# MCU.net
KiCad netlist of a schematic drawn in Altium Designer
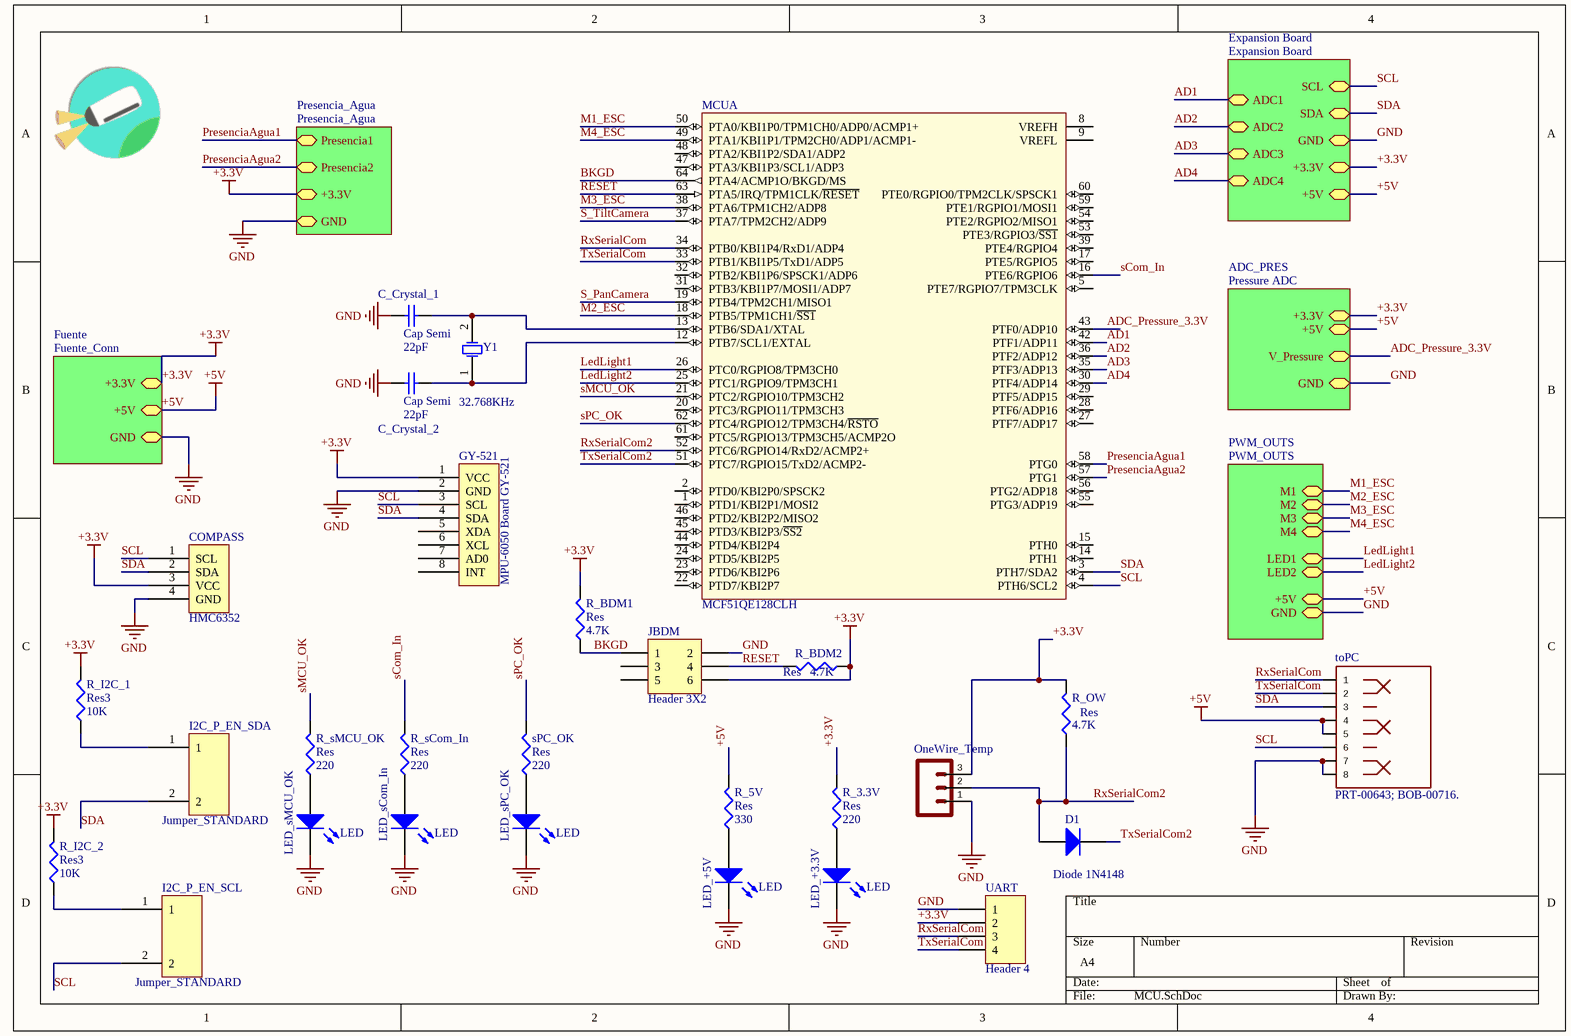
[diagram p0: MCU.SchDoc]

(export (version "E")
  (design (tool "Eeschema 10.0.6"))
  (components
    (comp (ref "COMPASS")
      (value "HMC6352")
      (footprint "HMC6352_SF")
      (libsource (lib "XSUB_COMP") (part "HMC6352"))
    )
    (comp (ref "C_Crystal_1")
      (value "Cap Semi")
      (footprint "1608[0603]")
      (description "Capacitor (Semiconductor SIM Model)")
      (fields (field (name "ALTIUM_VALUE") "22pF") (field (name "PUBLISHER") "Altium Limited"))
      (libsource (lib "Miscellaneous Devices") (part "Cap Semi"))
    )
    (comp (ref "C_Crystal_2")
      (value "Cap Semi")
      (footprint "1608[0603]")
      (description "Capacitor (Semiconductor SIM Model)")
      (fields (field (name "ALTIUM_VALUE") "22pF") (field (name "PUBLISHER") "Altium Limited"))
      (libsource (lib "Miscellaneous Devices") (part "Cap Semi"))
    )
    (comp (ref "D1")
      (value "Diode 1N4148")
      (footprint "DO-35")
      (description "High Conductance Fast Diode")
      (fields (field (name "PUBLISHER") "Altium Limited"))
      (libsource (lib "Miscellaneous Devices") (part "Diode 1N4148"))
    )
    (comp (ref "GY-521")
      (value "MPU-6050 Board GY-521")
      (footprint "GY-521")
      (libsource (lib "XSUB_COMP") (part "GY-521"))
    )
    (comp (ref "I2C_P_EN_SCL")
      (value "Jumper_STANDARD")
      (footprint "HDR1X2")
      (libsource (lib "XSUB_COMP") (part "Jumper_STANDAR"))
    )
    (comp (ref "I2C_P_EN_SDA")
      (value "Jumper_STANDARD")
      (footprint "HDR1X2")
      (libsource (lib "XSUB_COMP") (part "Jumper_STANDAR"))
    )
    (comp (ref "JBDM")
      (value "Header 3X2")
      (footprint "HDR2X3")
      (description "Header, 3-Pin, Dual row")
      (fields (field (name "PUBLISHER") "Altium Limited"))
      (libsource (lib "Miscellaneous Connectors") (part "Header 3X2"))
    )
    (comp (ref "LED_+3.3V")
      (value "LED")
      (footprint "3.2X1.6X1.1")
      (description "Typical RED, GREEN, YELLOW, AMBER GaAs LED")
      (fields (field (name "PUBLISHER") "Altium Limited"))
      (libsource (lib "Miscellaneous Devices") (part "LED2"))
    )
    (comp (ref "LED_+5V")
      (value "LED")
      (footprint "3.2X1.6X1.1")
      (description "Typical RED, GREEN, YELLOW, AMBER GaAs LED")
      (fields (field (name "PUBLISHER") "Altium Limited"))
      (libsource (lib "Miscellaneous Devices") (part "LED2"))
    )
    (comp (ref "LED_sCom_In")
      (value "LED")
      (footprint "3.2X1.6X1.1")
      (description "Typical RED, GREEN, YELLOW, AMBER GaAs LED")
      (fields (field (name "PUBLISHER") "Altium Limited"))
      (libsource (lib "Miscellaneous Devices") (part "LED2"))
    )
    (comp (ref "LED_sMCU_OK")
      (value "LED")
      (footprint "3.2X1.6X1.1")
      (description "Typical RED, GREEN, YELLOW, AMBER GaAs LED")
      (fields (field (name "PUBLISHER") "Altium Limited"))
      (libsource (lib "Miscellaneous Devices") (part "LED2"))
    )
    (comp (ref "LED_sPC_OK")
      (value "LED")
      (footprint "3.2X1.6X1.1")
      (description "Typical RED, GREEN, YELLOW, AMBER GaAs LED")
      (fields (field (name "PUBLISHER") "Altium Limited"))
      (libsource (lib "Miscellaneous Devices") (part "LED2"))
    )
    (comp (ref "MCU")
      (value "MCF51QE128CLH")
      (footprint "840F-02_N")
      (description "MCF51QE128 ColdFire V1 Microcontroller, 32-Bit, 128KB Flash, 8KB RAM, -40°C to 85°C, 64-Pin LQFP")
      (libsource (lib "Freescale Semiconductor ColdFire MCU") (part "MCF51QE128CLH"))
    )
    (comp (ref "OneWire_Temp")
      (value "~")
      (footprint "SCREWTERMINAL-5MM-3")
      (libsource (lib "SparkFun-Connectors") (part "M03-SCREW-5MM"))
    )
    (comp (ref "R_3.3V")
      (value "Res")
      (footprint "RESC6332")
      (description "Resistor")
      (fields (field (name "ALTIUM_VALUE") "220") (field (name "PUBLISHER") "Altium Limited"))
      (libsource (lib "Miscellaneous Devices") (part "Res3"))
    )
    (comp (ref "R_5V")
      (value "Res")
      (footprint "RESC6332")
      (description "Resistor")
      (fields (field (name "ALTIUM_VALUE") "330") (field (name "PUBLISHER") "Altium Limited"))
      (libsource (lib "Miscellaneous Devices") (part "Res3"))
    )
    (comp (ref "R_BDM1")
      (value "Res")
      (footprint "RESC6332")
      (description "Resistor")
      (fields (field (name "ALTIUM_VALUE") "4.7K") (field (name "PUBLISHER") "Altium Limited"))
      (libsource (lib "Miscellaneous Devices") (part "Res3"))
    )
    (comp (ref "R_BDM2")
      (value "Res")
      (footprint "RESC6332")
      (description "Resistor")
      (fields (field (name "ALTIUM_VALUE") "4.7K") (field (name "PUBLISHER") "Altium Limited"))
      (libsource (lib "Miscellaneous Devices") (part "Res3"))
    )
    (comp (ref "R_I2C_1")
      (value "Res3")
      (footprint "RESC6332")
      (description "Resistor")
      (fields (field (name "ALTIUM_VALUE") "10K") (field (name "PUBLISHER") "Altium Limited"))
      (libsource (lib "Miscellaneous Devices") (part "Res3"))
    )
    (comp (ref "R_I2C_2")
      (value "Res3")
      (footprint "RESC6332")
      (description "Resistor")
      (fields (field (name "ALTIUM_VALUE") "10K") (field (name "PUBLISHER") "Altium Limited"))
      (libsource (lib "Miscellaneous Devices") (part "Res3"))
    )
    (comp (ref "R_OW")
      (value "Res")
      (footprint "RESC6332")
      (description "Resistor")
      (fields (field (name "ALTIUM_VALUE") "4.7K") (field (name "PUBLISHER") "Altium Limited"))
      (libsource (lib "Miscellaneous Devices") (part "Res3"))
    )
    (comp (ref "R_sCom_In")
      (value "Res")
      (footprint "RESC6332")
      (description "Resistor")
      (fields (field (name "ALTIUM_VALUE") "220") (field (name "PUBLISHER") "Altium Limited"))
      (libsource (lib "Miscellaneous Devices") (part "Res3"))
    )
    (comp (ref "R_sMCU_OK")
      (value "Res")
      (footprint "RESC6332")
      (description "Resistor")
      (fields (field (name "ALTIUM_VALUE") "220") (field (name "PUBLISHER") "Altium Limited"))
      (libsource (lib "Miscellaneous Devices") (part "Res3"))
    )
    (comp (ref "sPC_OK")
      (value "Res")
      (footprint "RESC6332")
      (description "Resistor")
      (fields (field (name "ALTIUM_VALUE") "220") (field (name "PUBLISHER") "Altium Limited"))
      (libsource (lib "Miscellaneous Devices") (part "Res3"))
    )
    (comp (ref "toPC")
      (value "PRT-00643; BOB-00716.")
      (footprint "RJ45-8")
      (libsource (lib "SparkFun-Connectors") (part "RJ45-8PTH"))
    )
    (comp (ref "UART")
      (value "Header 4")
      (footprint "HDR1X4")
      (description "Header, 4-Pin")
      (fields (field (name "PUBLISHER") "Altium Limited"))
      (libsource (lib "Miscellaneous Connectors") (part "Header 4"))
    )
    (comp (ref "Y1")
      (value "32.768KHz")
      (footprint "R38")
      (description "Crystal Oscillator")
      (fields (field (name "PUBLISHER") "Altium Limited"))
      (libsource (lib "Miscellaneous Devices") (part "XTAL"))
    )
  )
  (nets
    (net (code "1") (name "+3.3V") (class "Default")
      (node (ref "COMPASS") (pin "3") (pinfunction "VCC_3") (pintype "passive"))
      (node (ref "GY-521") (pin "1") (pinfunction "VCC_1") (pintype "power_in"))
      (node (ref "JBDM") (pin "6") (pinfunction "6_6") (pintype "passive"))
      (node (ref "OneWire_Temp") (pin "3") (pinfunction "3_3") (pintype "passive"))
      (node (ref "R_3.3V") (pin "2") (pinfunction "2_2") (pintype "passive"))
      (node (ref "R_BDM1") (pin "2") (pinfunction "2_2") (pintype "passive"))
      (node (ref "R_BDM2") (pin "1") (pinfunction "1_1") (pintype "passive"))
      (node (ref "R_I2C_1") (pin "2") (pinfunction "2_2") (pintype "passive"))
      (node (ref "R_I2C_2") (pin "2") (pinfunction "2_2") (pintype "passive"))
      (node (ref "R_OW") (pin "2") (pinfunction "2_2") (pintype "passive"))
      (node (ref "UART") (pin "2") (pinfunction "2_2") (pintype "passive"))
    )
    (net (code "2") (name "+5V") (class "Default")
      (node (ref "R_5V") (pin "2") (pinfunction "2_2") (pintype "passive"))
      (node (ref "toPC") (pin "4") (pinfunction "4_4") (pintype "passive"))
      (node (ref "toPC") (pin "5") (pinfunction "5_5") (pintype "passive"))
    )
    (net (code "3") (name "/AD1") (class "Default")
      (node (ref "MCU") (pin "42") (pinfunction "PTF1/ADP11_42") (pintype "bidirectional"))
    )
    (net (code "4") (name "/AD2") (class "Default")
      (node (ref "MCU") (pin "36") (pinfunction "PTF2/ADP12_36") (pintype "bidirectional"))
    )
    (net (code "5") (name "/AD3") (class "Default")
      (node (ref "MCU") (pin "35") (pinfunction "PTF3/ADP13_35") (pintype "bidirectional"))
    )
    (net (code "6") (name "/AD4") (class "Default")
      (node (ref "MCU") (pin "30") (pinfunction "PTF4/ADP14_30") (pintype "bidirectional"))
    )
    (net (code "7") (name "/ADC_Pressure_3.3V") (class "Default")
      (node (ref "MCU") (pin "43") (pinfunction "PTF0/ADP10_43") (pintype "bidirectional"))
    )
    (net (code "8") (name "/BKGD") (class "Default")
      (node (ref "JBDM") (pin "1") (pinfunction "1_1") (pintype "passive"))
      (node (ref "MCU") (pin "64") (pinfunction "PTA4/ACMP1O/BKGD/MS_64") (pintype "output"))
      (node (ref "R_BDM1") (pin "1") (pinfunction "1_1") (pintype "passive"))
    )
    (net (code "9") (name "/LedLight1") (class "Default")
      (node (ref "MCU") (pin "26") (pinfunction "PTC0/RGPIO8/TPM3CH0_26") (pintype "bidirectional"))
    )
    (net (code "10") (name "/LedLight2") (class "Default")
      (node (ref "MCU") (pin "25") (pinfunction "PTC1/RGPIO9/TPM3CH1_25") (pintype "bidirectional"))
    )
    (net (code "11") (name "/M1_ESC") (class "Default")
      (node (ref "MCU") (pin "50") (pinfunction "PTA0/KBI1P0/TPM1CH0/ADP0/ACMP1+_50") (pintype "bidirectional"))
    )
    (net (code "12") (name "/M2_ESC") (class "Default")
      (node (ref "MCU") (pin "18") (pinfunction "PTB5/TPM1CH1/~{SS1}_18") (pintype "bidirectional"))
    )
    (net (code "13") (name "/M3_ESC") (class "Default")
      (node (ref "MCU") (pin "38") (pinfunction "PTA6/TPM1CH2/ADP8_38") (pintype "bidirectional"))
    )
    (net (code "14") (name "/M4_ESC") (class "Default")
      (node (ref "MCU") (pin "49") (pinfunction "PTA1/KBI1P1/TPM2CH0/ADP1/ACMP1-_49") (pintype "bidirectional"))
    )
    (net (code "15") (name "/PresenciaAgua1") (class "Default")
      (node (ref "MCU") (pin "58") (pinfunction "PTG0_58") (pintype "bidirectional"))
    )
    (net (code "16") (name "/PresenciaAgua2") (class "Default")
      (node (ref "MCU") (pin "57") (pinfunction "PTG1_57") (pintype "bidirectional"))
    )
    (net (code "17") (name "/RESET") (class "Default")
      (node (ref "JBDM") (pin "4") (pinfunction "4_4") (pintype "passive"))
      (node (ref "MCU") (pin "63") (pinfunction "PTA5/IRQ/TPM1CLK/~{RESET}_63") (pintype "input"))
      (node (ref "R_BDM2") (pin "2") (pinfunction "2_2") (pintype "passive"))
    )
    (net (code "18") (name "/RxSerialCom") (class "Default")
      (node (ref "MCU") (pin "34") (pinfunction "PTB0/KBI1P4/RxD1/ADP4_34") (pintype "bidirectional"))
      (node (ref "UART") (pin "3") (pinfunction "3_3") (pintype "passive"))
      (node (ref "toPC") (pin "1") (pinfunction "1_1") (pintype "passive"))
    )
    (net (code "19") (name "/RxSerialCom2") (class "Default")
      (node (ref "D1") (pin "1") (pinfunction "A_1") (pintype "passive"))
      (node (ref "MCU") (pin "52") (pinfunction "PTC6/RGPIO14/RxD2/ACMP2+_52") (pintype "bidirectional"))
      (node (ref "OneWire_Temp") (pin "2") (pinfunction "2_2") (pintype "passive"))
      (node (ref "R_OW") (pin "1") (pinfunction "1_1") (pintype "passive"))
    )
    (net (code "20") (name "/SCL") (class "Default")
      (node (ref "COMPASS") (pin "1") (pinfunction "SCL_1") (pintype "passive"))
      (node (ref "GY-521") (pin "3") (pinfunction "SCL_3") (pintype "passive"))
      (node (ref "I2C_P_EN_SCL") (pin "2") (pinfunction "2_2") (pintype "passive"))
      (node (ref "MCU") (pin "4") (pinfunction "PTH6/SCL2_4") (pintype "bidirectional"))
      (node (ref "toPC") (pin "6") (pinfunction "6_6") (pintype "passive"))
    )
    (net (code "21") (name "/SDA") (class "Default")
      (node (ref "COMPASS") (pin "2") (pinfunction "SDA_2") (pintype "passive"))
      (node (ref "GY-521") (pin "4") (pinfunction "SDA_4") (pintype "passive"))
      (node (ref "I2C_P_EN_SDA") (pin "2") (pinfunction "2_2") (pintype "passive"))
      (node (ref "MCU") (pin "3") (pinfunction "PTH7/SDA2_3") (pintype "bidirectional"))
      (node (ref "toPC") (pin "3") (pinfunction "3_3") (pintype "passive"))
    )
    (net (code "22") (name "/S_PanCamera") (class "Default")
      (node (ref "MCU") (pin "19") (pinfunction "PTB4/TPM2CH1/MISO1_19") (pintype "bidirectional"))
    )
    (net (code "23") (name "/S_TiltCamera") (class "Default")
      (node (ref "MCU") (pin "37") (pinfunction "PTA7/TPM2CH2/ADP9_37") (pintype "bidirectional"))
    )
    (net (code "24") (name "/TxSerialCom") (class "Default")
      (node (ref "MCU") (pin "33") (pinfunction "PTB1/KBI1P5/TxD1/ADP5_33") (pintype "bidirectional"))
      (node (ref "UART") (pin "4") (pinfunction "4_4") (pintype "passive"))
      (node (ref "toPC") (pin "2") (pinfunction "2_2") (pintype "passive"))
    )
    (net (code "25") (name "/TxSerialCom2") (class "Default")
      (node (ref "D1") (pin "2") (pinfunction "K_2") (pintype "passive"))
      (node (ref "MCU") (pin "51") (pinfunction "PTC7/RGPIO15/TxD2/ACMP2-_51") (pintype "bidirectional"))
    )
    (net (code "26") (name "/sCom_In") (class "Default")
      (node (ref "MCU") (pin "16") (pinfunction "PTE6/RGPIO6_16") (pintype "bidirectional"))
      (node (ref "R_sCom_In") (pin "2") (pinfunction "2_2") (pintype "passive"))
    )
    (net (code "27") (name "/sMCU_OK") (class "Default")
      (node (ref "MCU") (pin "21") (pinfunction "PTC2/RGPIO10/TPM3CH2_21") (pintype "bidirectional"))
      (node (ref "R_sMCU_OK") (pin "2") (pinfunction "2_2") (pintype "passive"))
    )
    (net (code "28") (name "/sPC_OK") (class "Default")
      (node (ref "MCU") (pin "62") (pinfunction "PTC4/RGPIO12/TPM3CH4/~{RSTO}_62") (pintype "bidirectional"))
      (node (ref "sPC_OK") (pin "2") (pinfunction "2_2") (pintype "passive"))
    )
    (net (code "29") (name "GND") (class "Default")
      (node (ref "COMPASS") (pin "4") (pinfunction "GND_4") (pintype "passive"))
      (node (ref "C_Crystal_1") (pin "1") (pinfunction "1_1") (pintype "passive"))
      (node (ref "C_Crystal_2") (pin "1") (pinfunction "1_1") (pintype "passive"))
      (node (ref "GY-521") (pin "2") (pinfunction "GND_2") (pintype "power_in"))
      (node (ref "JBDM") (pin "2") (pinfunction "2_2") (pintype "passive"))
      (node (ref "LED_+3.3V") (pin "2") (pinfunction "K_2") (pintype "passive"))
      (node (ref "LED_+5V") (pin "2") (pinfunction "K_2") (pintype "passive"))
      (node (ref "LED_sCom_In") (pin "2") (pinfunction "K_2") (pintype "passive"))
      (node (ref "LED_sMCU_OK") (pin "2") (pinfunction "K_2") (pintype "passive"))
      (node (ref "LED_sPC_OK") (pin "2") (pinfunction "K_2") (pintype "passive"))
      (node (ref "OneWire_Temp") (pin "1") (pinfunction "1_1") (pintype "passive"))
      (node (ref "UART") (pin "1") (pinfunction "1_1") (pintype "passive"))
      (node (ref "toPC") (pin "7") (pinfunction "7_7") (pintype "passive"))
      (node (ref "toPC") (pin "8") (pinfunction "8_8") (pintype "passive"))
    )
    (net (code "30") (name "Net-(I2C_P_EN_SCL-Pad1)") (class "Default")
      (node (ref "I2C_P_EN_SCL") (pin "1") (pinfunction "1_1") (pintype "passive"))
      (node (ref "R_I2C_2") (pin "1") (pinfunction "1_1") (pintype "passive"))
    )
    (net (code "31") (name "Net-(I2C_P_EN_SDA-Pad1)") (class "Default")
      (node (ref "I2C_P_EN_SDA") (pin "1") (pinfunction "1_1") (pintype "passive"))
      (node (ref "R_I2C_1") (pin "1") (pinfunction "1_1") (pintype "passive"))
    )
    (net (code "32") (name "Net-(LED_+3.3V-A)") (class "Default")
      (node (ref "LED_+3.3V") (pin "1") (pinfunction "A_1") (pintype "passive"))
      (node (ref "R_3.3V") (pin "1") (pinfunction "1_1") (pintype "passive"))
    )
    (net (code "33") (name "Net-(LED_+5V-A)") (class "Default")
      (node (ref "LED_+5V") (pin "1") (pinfunction "A_1") (pintype "passive"))
      (node (ref "R_5V") (pin "1") (pinfunction "1_1") (pintype "passive"))
    )
    (net (code "34") (name "Net-(LED_sCom_In-A)") (class "Default")
      (node (ref "LED_sCom_In") (pin "1") (pinfunction "A_1") (pintype "passive"))
      (node (ref "R_sCom_In") (pin "1") (pinfunction "1_1") (pintype "passive"))
    )
    (net (code "35") (name "Net-(LED_sMCU_OK-A)") (class "Default")
      (node (ref "LED_sMCU_OK") (pin "1") (pinfunction "A_1") (pintype "passive"))
      (node (ref "R_sMCU_OK") (pin "1") (pinfunction "1_1") (pintype "passive"))
    )
    (net (code "36") (name "Net-(LED_sPC_OK-A)") (class "Default")
      (node (ref "LED_sPC_OK") (pin "1") (pinfunction "A_1") (pintype "passive"))
      (node (ref "sPC_OK") (pin "1") (pinfunction "1_1") (pintype "passive"))
    )
    (net (code "37") (name "Net-(MCUA-PTB6{slash}SDA1{slash}XTAL)") (class "Default")
      (node (ref "C_Crystal_1") (pin "2") (pinfunction "2_2") (pintype "passive"))
      (node (ref "MCU") (pin "13") (pinfunction "PTB6/SDA1/XTAL_13") (pintype "bidirectional"))
      (node (ref "Y1") (pin "2") (pinfunction "OSC2_2") (pintype "passive"))
    )
    (net (code "38") (name "Net-(MCUA-PTB7{slash}SCL1{slash}EXTAL)") (class "Default")
      (node (ref "C_Crystal_2") (pin "2") (pinfunction "2_2") (pintype "passive"))
      (node (ref "MCU") (pin "12") (pinfunction "PTB7/SCL1/EXTAL_12") (pintype "bidirectional"))
      (node (ref "Y1") (pin "1") (pinfunction "OSC1_1") (pintype "passive"))
    )
    (net (code "39") (name "unconnected-(GY-521-AD0-Pad7)") (class "Default")
      (node (ref "GY-521") (pin "7") (pinfunction "AD0_7") (pintype "passive"))
    )
    (net (code "40") (name "unconnected-(GY-521-INT-Pad8)") (class "Default")
      (node (ref "GY-521") (pin "8") (pinfunction "INT_8") (pintype "passive"))
    )
    (net (code "41") (name "unconnected-(GY-521-XCL-Pad6)") (class "Default")
      (node (ref "GY-521") (pin "6") (pinfunction "XCL_6") (pintype "passive"))
    )
    (net (code "42") (name "unconnected-(GY-521-XDA-Pad5)") (class "Default")
      (node (ref "GY-521") (pin "5") (pinfunction "XDA_5") (pintype "passive"))
    )
    (net (code "43") (name "unconnected-(JBDM-Pad3)") (class "Default")
      (node (ref "JBDM") (pin "3") (pinfunction "3_3") (pintype "passive"))
    )
    (net (code "44") (name "unconnected-(JBDM-Pad5)") (class "Default")
      (node (ref "JBDM") (pin "5") (pinfunction "5_5") (pintype "passive"))
    )
    (net (code "45") (name "unconnected-(MCUA-PTA2{slash}KBI1P2{slash}SDA1{slash}ADP2-Pad48)") (class "Default")
      (node (ref "MCU") (pin "48") (pinfunction "PTA2/KBI1P2/SDA1/ADP2_48") (pintype "bidirectional"))
    )
    (net (code "46") (name "unconnected-(MCUA-PTA3{slash}KBI1P3{slash}SCL1{slash}ADP3-Pad47)") (class "Default")
      (node (ref "MCU") (pin "47") (pinfunction "PTA3/KBI1P3/SCL1/ADP3_47") (pintype "bidirectional"))
    )
    (net (code "47") (name "unconnected-(MCUA-PTB2{slash}KBI1P6{slash}SPSCK1{slash}ADP6-Pad32)") (class "Default")
      (node (ref "MCU") (pin "32") (pinfunction "PTB2/KBI1P6/SPSCK1/ADP6_32") (pintype "bidirectional"))
    )
    (net (code "48") (name "unconnected-(MCUA-PTB3{slash}KBI1P7{slash}MOSI1{slash}ADP7-Pad31)") (class "Default")
      (node (ref "MCU") (pin "31") (pinfunction "PTB3/KBI1P7/MOSI1/ADP7_31") (pintype "bidirectional"))
    )
    (net (code "49") (name "unconnected-(MCUA-PTC3{slash}RGPIO11{slash}TPM3CH3-Pad20)") (class "Default")
      (node (ref "MCU") (pin "20") (pinfunction "PTC3/RGPIO11/TPM3CH3_20") (pintype "bidirectional"))
    )
    (net (code "50") (name "unconnected-(MCUA-PTC5{slash}RGPIO13{slash}TPM3CH5{slash}ACMP2O-Pad61)") (class "Default")
      (node (ref "MCU") (pin "61") (pinfunction "PTC5/RGPIO13/TPM3CH5/ACMP2O_61") (pintype "bidirectional"))
    )
    (net (code "51") (name "unconnected-(MCUA-PTD0{slash}KBI2P0{slash}SPSCK2-Pad2)") (class "Default")
      (node (ref "MCU") (pin "2") (pinfunction "PTD0/KBI2P0/SPSCK2_2") (pintype "bidirectional"))
    )
    (net (code "52") (name "unconnected-(MCUA-PTD1{slash}KBI2P1{slash}MOSI2-Pad1)") (class "Default")
      (node (ref "MCU") (pin "1") (pinfunction "PTD1/KBI2P1/MOSI2_1") (pintype "bidirectional"))
    )
    (net (code "53") (name "unconnected-(MCUA-PTD2{slash}KBI2P2{slash}MISO2-Pad46)") (class "Default")
      (node (ref "MCU") (pin "46") (pinfunction "PTD2/KBI2P2/MISO2_46") (pintype "bidirectional"))
    )
    (net (code "54") (name "unconnected-(MCUA-PTD3{slash}KBI2P3{slash}~{SS2}-Pad45)") (class "Default")
      (node (ref "MCU") (pin "45") (pinfunction "PTD3/KBI2P3/~{SS2}_45") (pintype "bidirectional"))
    )
    (net (code "55") (name "unconnected-(MCUA-PTD4{slash}KBI2P4-Pad44)") (class "Default")
      (node (ref "MCU") (pin "44") (pinfunction "PTD4/KBI2P4_44") (pintype "bidirectional"))
    )
    (net (code "56") (name "unconnected-(MCUA-PTD5{slash}KBI2P5-Pad24)") (class "Default")
      (node (ref "MCU") (pin "24") (pinfunction "PTD5/KBI2P5_24") (pintype "bidirectional"))
    )
    (net (code "57") (name "unconnected-(MCUA-PTD6{slash}KBI2P6-Pad23)") (class "Default")
      (node (ref "MCU") (pin "23") (pinfunction "PTD6/KBI2P6_23") (pintype "bidirectional"))
    )
    (net (code "58") (name "unconnected-(MCUA-PTD7{slash}KBI2P7-Pad22)") (class "Default")
      (node (ref "MCU") (pin "22") (pinfunction "PTD7/KBI2P7_22") (pintype "bidirectional"))
    )
    (net (code "59") (name "unconnected-(MCUA-PTE0{slash}RGPIO0{slash}TPM2CLK{slash}SPSCK1-Pad60)") (class "Default")
      (node (ref "MCU") (pin "60") (pinfunction "PTE0/RGPIO0/TPM2CLK/SPSCK1_60") (pintype "bidirectional"))
    )
    (net (code "60") (name "unconnected-(MCUA-PTE1{slash}RGPIO1{slash}MOSI1-Pad59)") (class "Default")
      (node (ref "MCU") (pin "59") (pinfunction "PTE1/RGPIO1/MOSI1_59") (pintype "bidirectional"))
    )
    (net (code "61") (name "unconnected-(MCUA-PTE2{slash}RGPIO2{slash}MISO1-Pad54)") (class "Default")
      (node (ref "MCU") (pin "54") (pinfunction "PTE2/RGPIO2/MISO1_54") (pintype "bidirectional"))
    )
    (net (code "62") (name "unconnected-(MCUA-PTE3{slash}RGPIO3{slash}~{SS1}-Pad53)") (class "Default")
      (node (ref "MCU") (pin "53") (pinfunction "PTE3/RGPIO3/~{SS1}_53") (pintype "bidirectional"))
    )
    (net (code "63") (name "unconnected-(MCUA-PTE4{slash}RGPIO4-Pad39)") (class "Default")
      (node (ref "MCU") (pin "39") (pinfunction "PTE4/RGPIO4_39") (pintype "bidirectional"))
    )
    (net (code "64") (name "unconnected-(MCUA-PTE5{slash}RGPIO5-Pad17)") (class "Default")
      (node (ref "MCU") (pin "17") (pinfunction "PTE5/RGPIO5_17") (pintype "bidirectional"))
    )
    (net (code "65") (name "unconnected-(MCUA-PTE7{slash}RGPIO7{slash}TPM3CLK-Pad5)") (class "Default")
      (node (ref "MCU") (pin "5") (pinfunction "PTE7/RGPIO7/TPM3CLK_5") (pintype "bidirectional"))
    )
    (net (code "66") (name "unconnected-(MCUA-PTF5{slash}ADP15-Pad29)") (class "Default")
      (node (ref "MCU") (pin "29") (pinfunction "PTF5/ADP15_29") (pintype "bidirectional"))
    )
    (net (code "67") (name "unconnected-(MCUA-PTF6{slash}ADP16-Pad28)") (class "Default")
      (node (ref "MCU") (pin "28") (pinfunction "PTF6/ADP16_28") (pintype "bidirectional"))
    )
    (net (code "68") (name "unconnected-(MCUA-PTF7{slash}ADP17-Pad27)") (class "Default")
      (node (ref "MCU") (pin "27") (pinfunction "PTF7/ADP17_27") (pintype "bidirectional"))
    )
    (net (code "69") (name "unconnected-(MCUA-PTG2{slash}ADP18-Pad56)") (class "Default")
      (node (ref "MCU") (pin "56") (pinfunction "PTG2/ADP18_56") (pintype "bidirectional"))
    )
    (net (code "70") (name "unconnected-(MCUA-PTG3{slash}ADP19-Pad55)") (class "Default")
      (node (ref "MCU") (pin "55") (pinfunction "PTG3/ADP19_55") (pintype "bidirectional"))
    )
    (net (code "71") (name "unconnected-(MCUA-PTH0-Pad15)") (class "Default")
      (node (ref "MCU") (pin "15") (pinfunction "PTH0_15") (pintype "bidirectional"))
    )
    (net (code "72") (name "unconnected-(MCUA-PTH1-Pad14)") (class "Default")
      (node (ref "MCU") (pin "14") (pinfunction "PTH1_14") (pintype "bidirectional"))
    )
    (net (code "73") (name "unconnected-(MCUA-VREFH-Pad8)") (class "Default")
      (node (ref "MCU") (pin "8") (pinfunction "VREFH_8") (pintype "passive"))
    )
    (net (code "74") (name "unconnected-(MCUA-VREFL-Pad9)") (class "Default")
      (node (ref "MCU") (pin "9") (pinfunction "VREFL_9") (pintype "passive"))
    )
  )
)
